# pH_tl082_v3.net
KiCad netlist of a schematic drawn in EAGLE
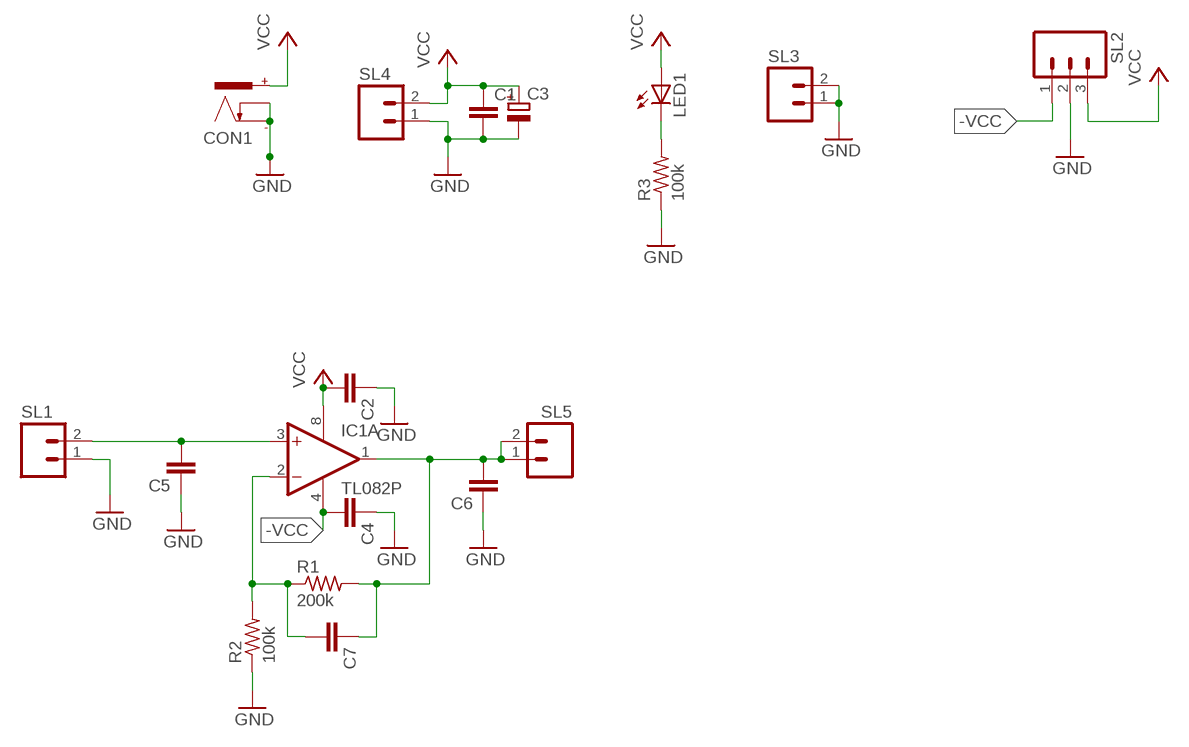
[diagram p0: schematic, sheet 1]

(export (version "E")
  (design (tool "Eeschema 10.0.6"))
  (components
    (comp (ref "C1")
      (value "C2.5/2")
      (footprint "eagle-import:C2.5-2")
      (libsource (lib "eagle-import") (part "C2.5/2"))
    )
    (comp (ref "C2")
      (value "C2.5/2")
      (footprint "eagle-import:C2.5-2")
      (libsource (lib "eagle-import") (part "C2.5/2"))
    )
    (comp (ref "C3")
      (value "CPOL-EUE2,5-6E")
      (footprint "eagle-import:E2,5-6E")
      (libsource (lib "eagle-import") (part "CPOL-EUE2,5-6E"))
    )
    (comp (ref "C4")
      (value "C2.5/2")
      (footprint "eagle-import:C2.5-2")
      (libsource (lib "eagle-import") (part "C2.5/2"))
    )
    (comp (ref "C5")
      (value "C2.5/2")
      (footprint "eagle-import:C2.5-2")
      (libsource (lib "eagle-import") (part "C2.5/2"))
    )
    (comp (ref "C6")
      (value "C2.5/2")
      (footprint "eagle-import:C2.5-2")
      (libsource (lib "eagle-import") (part "C2.5/2"))
    )
    (comp (ref "C7")
      (value "C2.5/2")
      (footprint "eagle-import:C2.5-2")
      (libsource (lib "eagle-import") (part "C2.5/2"))
    )
    (comp (ref "CON1")
      (value "POWER_CON")
      (footprint "eagle-import:NEB21R")
      (libsource (lib "eagle-import") (part "POWER_CON"))
    )
    (comp (ref "IC1")
      (value "TL082P")
      (footprint "eagle-import:DIL08")
      (libsource (lib "eagle-import") (part "TL082P"))
    )
    (comp (ref "LED1")
      (value "LED3MM")
      (footprint "eagle-import:LED3MM")
      (libsource (lib "eagle-import") (part "LED3MM"))
    )
    (comp (ref "R1")
      (value "200k")
      (footprint "eagle-import:0207_7")
      (libsource (lib "eagle-import") (part "RESISTOR0207/7"))
    )
    (comp (ref "R2")
      (value "100k")
      (footprint "eagle-import:0207_7")
      (libsource (lib "eagle-import") (part "RESISTOR0207/7"))
    )
    (comp (ref "R3")
      (value "100k")
      (footprint "eagle-import:0207_7")
      (libsource (lib "eagle-import") (part "RESISTOR0207/7"))
    )
    (comp (ref "SL1")
      (value "M02")
      (footprint "eagle-import:02P")
      (libsource (lib "eagle-import") (part "con-amp-quick_125_M02"))
    )
    (comp (ref "SL2")
      (value "M03")
      (footprint "eagle-import:03P")
      (libsource (lib "eagle-import") (part "M03"))
    )
    (comp (ref "SL3")
      (value "M02")
      (footprint "eagle-import:02P")
      (libsource (lib "eagle-import") (part "con-amp-quick_125_M02"))
    )
    (comp (ref "SL4")
      (value "M02")
      (footprint "eagle-import:02P")
      (libsource (lib "eagle-import") (part "M02"))
    )
    (comp (ref "SL5")
      (value "M02")
      (footprint "eagle-import:02P")
      (libsource (lib "eagle-import") (part "con-amp-quick_125_M02"))
    )
  )
  (nets
    (net (code "1") (name "-VCC") (class "Default")
      (node (ref "C4") (pin "2") (pinfunction "2_2") (pintype "passive"))
      (node (ref "IC1") (pin "4") (pinfunction "V-_4") (pintype "power_in"))
      (node (ref "SL2") (pin "1") (pinfunction "1_1") (pintype "passive"))
    )
    (net (code "2") (name "GND") (class "Default")
      (node (ref "C1") (pin "2") (pinfunction "2_2") (pintype "passive"))
      (node (ref "C2") (pin "1") (pinfunction "1_1") (pintype "passive"))
      (node (ref "C3") (pin "-") (pinfunction "-_-") (pintype "passive"))
      (node (ref "C4") (pin "1") (pinfunction "1_1") (pintype "passive"))
      (node (ref "C5") (pin "1") (pinfunction "1_1") (pintype "passive"))
      (node (ref "C6") (pin "1") (pinfunction "1_1") (pintype "passive"))
      (node (ref "CON1") (pin "-") (pinfunction "-_-") (pintype "passive"))
      (node (ref "CON1") (pin "C") (pinfunction "C_C") (pintype "passive"))
      (node (ref "R2") (pin "1") (pinfunction "1_1") (pintype "passive"))
      (node (ref "R3") (pin "1") (pinfunction "1_1") (pintype "passive"))
      (node (ref "SL1") (pin "1") (pinfunction "1_1") (pintype "passive"))
      (node (ref "SL2") (pin "2") (pinfunction "2_2") (pintype "passive"))
      (node (ref "SL3") (pin "1") (pinfunction "1_1") (pintype "passive"))
      (node (ref "SL3") (pin "2") (pinfunction "2_2") (pintype "passive"))
      (node (ref "SL4") (pin "1") (pinfunction "1_1") (pintype "passive"))
    )
    (net (code "3") (name "Net-(IC1A-+IN)") (class "Default")
      (node (ref "C5") (pin "2") (pinfunction "2_2") (pintype "passive"))
      (node (ref "IC1") (pin "3") (pinfunction "+IN_3") (pintype "input"))
      (node (ref "SL1") (pin "2") (pinfunction "2_2") (pintype "passive"))
    )
    (net (code "4") (name "Net-(IC1A--IN)") (class "Default")
      (node (ref "C7") (pin "2") (pinfunction "2_2") (pintype "passive"))
      (node (ref "IC1") (pin "2") (pinfunction "-IN_2") (pintype "input"))
      (node (ref "R1") (pin "1") (pinfunction "1_1") (pintype "passive"))
      (node (ref "R2") (pin "2") (pinfunction "2_2") (pintype "passive"))
    )
    (net (code "5") (name "Net-(IC1A-OUT)") (class "Default")
      (node (ref "C6") (pin "2") (pinfunction "2_2") (pintype "passive"))
      (node (ref "C7") (pin "1") (pinfunction "1_1") (pintype "passive"))
      (node (ref "IC1") (pin "1") (pinfunction "OUT_1") (pintype "output"))
      (node (ref "R1") (pin "2") (pinfunction "2_2") (pintype "passive"))
      (node (ref "SL5") (pin "1") (pinfunction "1_1") (pintype "passive"))
      (node (ref "SL5") (pin "2") (pinfunction "2_2") (pintype "passive"))
    )
    (net (code "6") (name "Net-(LED1-C)") (class "Default")
      (node (ref "LED1") (pin "K") (pinfunction "C_K") (pintype "passive"))
      (node (ref "R3") (pin "2") (pinfunction "2_2") (pintype "passive"))
    )
    (net (code "7") (name "VCC") (class "Default")
      (node (ref "C1") (pin "1") (pinfunction "1_1") (pintype "passive"))
      (node (ref "C2") (pin "2") (pinfunction "2_2") (pintype "passive"))
      (node (ref "C3") (pin "+") (pinfunction "+_+") (pintype "passive"))
      (node (ref "CON1") (pin "+") (pinfunction "+_+") (pintype "passive"))
      (node (ref "IC1") (pin "8") (pinfunction "V+_8") (pintype "power_in"))
      (node (ref "LED1") (pin "A") (pinfunction "A_A") (pintype "passive"))
      (node (ref "SL2") (pin "3") (pinfunction "3_3") (pintype "passive"))
      (node (ref "SL4") (pin "2") (pinfunction "2_2") (pintype "passive"))
    )
  )
)
